# buck_breakout.net
KiCad netlist of a schematic drawn in EAGLE
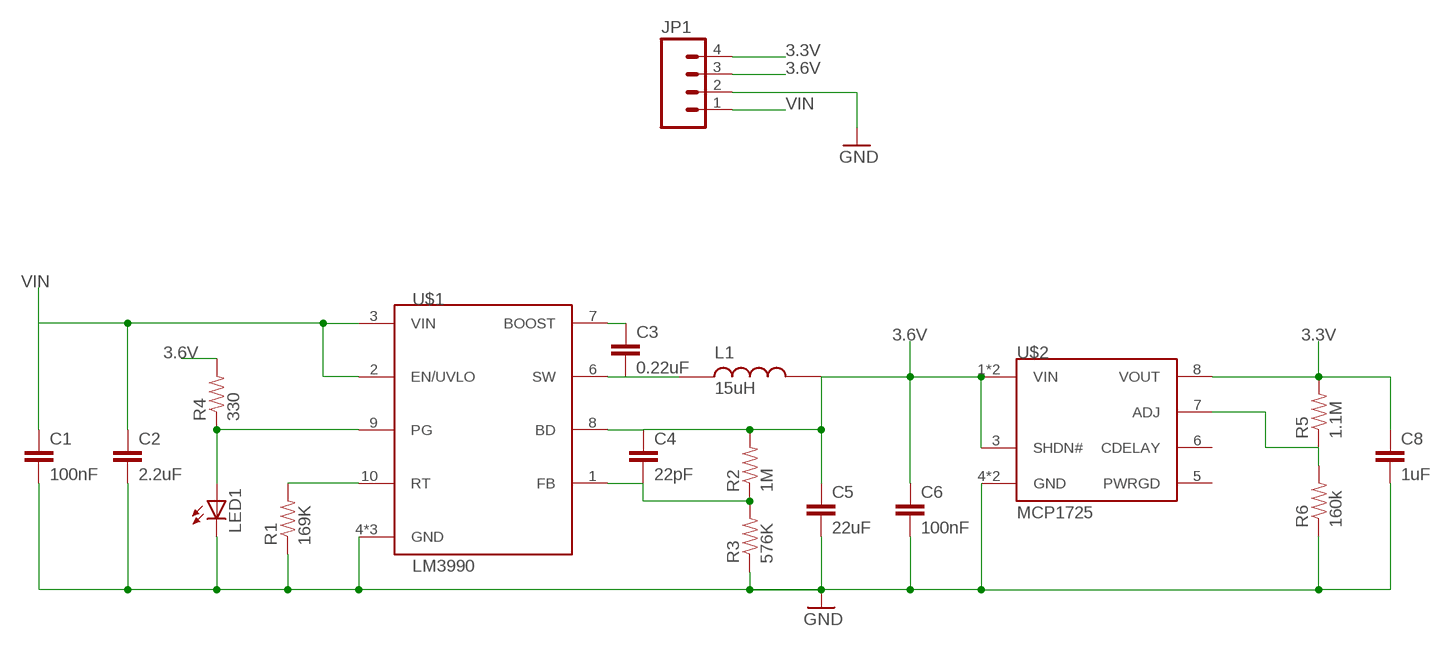
[diagram p0: schematic, sheet 1]

(export (version "E")
  (design (tool "Eeschema 10.0.6"))
  (components
    (comp (ref "C1")
      (value "100nF")
      (footprint "eagle-import:0603-CAP")
      (libsource (lib "eagle-import") (part "CAP0603-CAP"))
    )
    (comp (ref "C2")
      (value "2.2uF")
      (footprint "eagle-import:1206")
      (libsource (lib "eagle-import") (part "CAP1206"))
    )
    (comp (ref "C3")
      (value "0.22uF")
      (footprint "eagle-import:0603-CAP")
      (libsource (lib "eagle-import") (part "CAP0603-CAP"))
    )
    (comp (ref "C4")
      (value "22pF")
      (footprint "eagle-import:0603-CAP")
      (libsource (lib "eagle-import") (part "CAP0603-CAP"))
    )
    (comp (ref "C5")
      (value "22uF")
      (footprint "eagle-import:1206")
      (libsource (lib "eagle-import") (part "CAP1206"))
    )
    (comp (ref "C6")
      (value "100nF")
      (footprint "eagle-import:0603-CAP")
      (libsource (lib "eagle-import") (part "CAP0603-CAP"))
    )
    (comp (ref "C8")
      (value "1uF")
      (footprint "eagle-import:0603-CAP")
      (libsource (lib "eagle-import") (part "CAP0603-CAP"))
    )
    (comp (ref "JP1")
      (value "M04PTH")
      (footprint "eagle-import:1X04")
      (libsource (lib "eagle-import") (part "M04PTH"))
    )
    (comp (ref "L1")
      (value "15uH")
      (footprint "eagle-import:NR6028T150M")
      (libsource (lib "eagle-import") (part "NR6028T150M"))
    )
    (comp (ref "LED1")
      (value "LED0603")
      (footprint "eagle-import:LED-0603")
      (libsource (lib "eagle-import") (part "LED0603"))
    )
    (comp (ref "R1")
      (value "169K")
      (footprint "eagle-import:0402-S")
      (libsource (lib "eagle-import") (part "RESISTOR0402-S"))
    )
    (comp (ref "R2")
      (value "1M")
      (footprint "eagle-import:0402-S")
      (libsource (lib "eagle-import") (part "RESISTOR0402-S"))
    )
    (comp (ref "R3")
      (value "576K")
      (footprint "eagle-import:0402-S")
      (libsource (lib "eagle-import") (part "RESISTOR0402-S"))
    )
    (comp (ref "R4")
      (value "330")
      (footprint "eagle-import:0402-S")
      (libsource (lib "eagle-import") (part "RESISTOR0402-S"))
    )
    (comp (ref "R5")
      (value "1.1M")
      (footprint "eagle-import:0402-S")
      (libsource (lib "eagle-import") (part "RESISTOR0402-S"))
    )
    (comp (ref "R6")
      (value "160k")
      (footprint "eagle-import:0402-S")
      (libsource (lib "eagle-import") (part "RESISTOR0402-S"))
    )
    (comp (ref "U$1")
      (value "LM3990")
      (footprint "eagle-import:DD10")
      (libsource (lib "eagle-import") (part "LM3990"))
    )
    (comp (ref "U$2")
      (value "MCP1725")
      (footprint "eagle-import:2X3_DFN")
      (libsource (lib "eagle-import") (part "MCP1725"))
    )
  )
  (nets
    (net (code "1") (name "/3.3V") (class "Default")
      (node (ref "C8") (pin "1") (pinfunction "1_1") (pintype "passive"))
      (node (ref "JP1") (pin "4") (pinfunction "4_4") (pintype "passive"))
      (node (ref "R5") (pin "2") (pinfunction "2_2") (pintype "passive"))
      (node (ref "U$2") (pin "8") (pinfunction "VOUT_8") (pintype "bidirectional"))
    )
    (net (code "2") (name "/3.6V") (class "Default")
      (node (ref "C4") (pin "1") (pinfunction "1_1") (pintype "passive"))
      (node (ref "C5") (pin "1") (pinfunction "1_1") (pintype "passive"))
      (node (ref "C6") (pin "1") (pinfunction "1_1") (pintype "passive"))
      (node (ref "JP1") (pin "3") (pinfunction "3_3") (pintype "passive"))
      (node (ref "L1") (pin "2") (pinfunction "2_2") (pintype "bidirectional"))
      (node (ref "R2") (pin "2") (pinfunction "2_2") (pintype "passive"))
      (node (ref "R4") (pin "2") (pinfunction "2_2") (pintype "passive"))
      (node (ref "U$1") (pin "8") (pinfunction "BD_8") (pintype "bidirectional"))
      (node (ref "U$2") (pin "1") (pinfunction "VIN_1") (pintype "bidirectional"))
      (node (ref "U$2") (pin "2") (pinfunction "VIN_2") (pintype "bidirectional"))
      (node (ref "U$2") (pin "3") (pinfunction "SHDN#_3") (pintype "bidirectional"))
    )
    (net (code "3") (name "/VIN") (class "Default")
      (node (ref "C1") (pin "1") (pinfunction "1_1") (pintype "passive"))
      (node (ref "C2") (pin "1") (pinfunction "1_1") (pintype "passive"))
      (node (ref "JP1") (pin "1") (pinfunction "1_1") (pintype "passive"))
      (node (ref "U$1") (pin "2") (pinfunction "EN/UVLO_2") (pintype "bidirectional"))
      (node (ref "U$1") (pin "3") (pinfunction "VIN_3") (pintype "bidirectional"))
    )
    (net (code "4") (name "GND") (class "Default")
      (node (ref "C1") (pin "2") (pinfunction "2_2") (pintype "passive"))
      (node (ref "C2") (pin "2") (pinfunction "2_2") (pintype "passive"))
      (node (ref "C5") (pin "2") (pinfunction "2_2") (pintype "passive"))
      (node (ref "C6") (pin "2") (pinfunction "2_2") (pintype "passive"))
      (node (ref "C8") (pin "2") (pinfunction "2_2") (pintype "passive"))
      (node (ref "JP1") (pin "2") (pinfunction "2_2") (pintype "passive"))
      (node (ref "LED1") (pin "C") (pinfunction "C_C") (pintype "passive"))
      (node (ref "R1") (pin "1") (pinfunction "1_1") (pintype "passive"))
      (node (ref "R3") (pin "1") (pinfunction "1_1") (pintype "passive"))
      (node (ref "R6") (pin "1") (pinfunction "1_1") (pintype "passive"))
      (node (ref "U$1") (pin "4") (pinfunction "GND_4") (pintype "bidirectional"))
      (node (ref "U$1") (pin "5") (pinfunction "GND_5") (pintype "bidirectional"))
      (node (ref "U$1") (pin "EP\\") (pinfunction "GND_EP\\") (pintype "bidirectional"))
      (node (ref "U$2") (pin "4") (pinfunction "GND_4") (pintype "bidirectional"))
      (node (ref "U$2") (pin "EP") (pinfunction "GND_EP") (pintype "bidirectional"))
    )
    (net (code "5") (name "Net-(U$1-BOOST)") (class "Default")
      (node (ref "C3") (pin "1") (pinfunction "1_1") (pintype "passive"))
      (node (ref "U$1") (pin "7") (pinfunction "BOOST_7") (pintype "bidirectional"))
    )
    (net (code "6") (name "Net-(U$1-FB)") (class "Default")
      (node (ref "C4") (pin "2") (pinfunction "2_2") (pintype "passive"))
      (node (ref "R2") (pin "1") (pinfunction "1_1") (pintype "passive"))
      (node (ref "R3") (pin "2") (pinfunction "2_2") (pintype "passive"))
      (node (ref "U$1") (pin "1") (pinfunction "FB_1") (pintype "bidirectional"))
    )
    (net (code "7") (name "Net-(U$1-PG)") (class "Default")
      (node (ref "LED1") (pin "A") (pinfunction "A_A") (pintype "passive"))
      (node (ref "R4") (pin "1") (pinfunction "1_1") (pintype "passive"))
      (node (ref "U$1") (pin "9") (pinfunction "PG_9") (pintype "bidirectional"))
    )
    (net (code "8") (name "Net-(U$1-RT)") (class "Default")
      (node (ref "R1") (pin "2") (pinfunction "2_2") (pintype "passive"))
      (node (ref "U$1") (pin "10") (pinfunction "RT_10") (pintype "bidirectional"))
    )
    (net (code "9") (name "Net-(U$1-SW)") (class "Default")
      (node (ref "C3") (pin "2") (pinfunction "2_2") (pintype "passive"))
      (node (ref "L1") (pin "1") (pinfunction "1_1") (pintype "bidirectional"))
      (node (ref "U$1") (pin "6") (pinfunction "SW_6") (pintype "bidirectional"))
    )
    (net (code "10") (name "Net-(U$2-ADJ)") (class "Default")
      (node (ref "R5") (pin "1") (pinfunction "1_1") (pintype "passive"))
      (node (ref "R6") (pin "2") (pinfunction "2_2") (pintype "passive"))
      (node (ref "U$2") (pin "7") (pinfunction "ADJ_7") (pintype "bidirectional"))
    )
    (net (code "11") (name "unconnected-(U$2-CDELAY-Pad6)") (class "Default")
      (node (ref "U$2") (pin "6") (pinfunction "CDELAY_6") (pintype "bidirectional"))
    )
    (net (code "12") (name "unconnected-(U$2-PWRGD-Pad5)") (class "Default")
      (node (ref "U$2") (pin "5") (pinfunction "PWRGD_5") (pintype "bidirectional"))
    )
  )
)
